# projeto_final.net
KiCad netlist of a schematic drawn in EAGLE
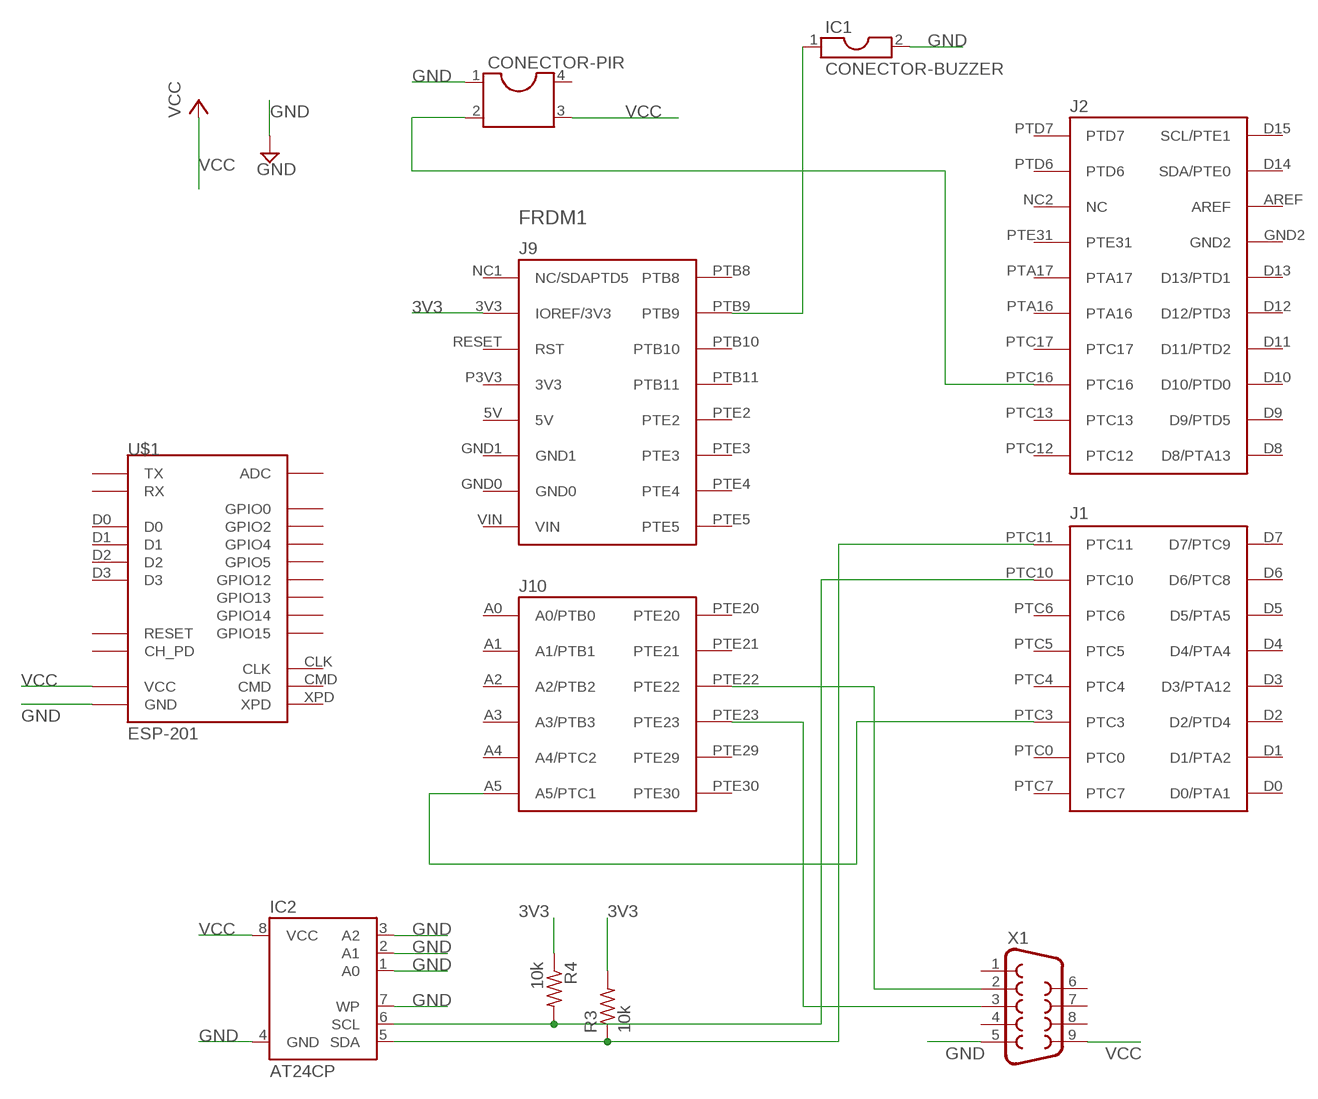
[diagram p0: schematic, sheet 1]

(export (version "E")
  (design (tool "Eeschema 10.0.6"))
  (components
    (comp (ref "CONECTOR-PIR")
      (value "DIL4")
      (footprint "eagle-import:DIL04")
      (libsource (lib "eagle-import") (part "DIL4"))
    )
    (comp (ref "FRDM1")
      (value "FRDM-KL25ZNORMAL")
      (footprint "eagle-import:FRDM_KL25Z_NORMAL")
      (libsource (lib "eagle-import") (part "FRDM-KL25ZNORMAL"))
    )
    (comp (ref "IC1")
      (value "CONECTOR-BUZZER")
      (footprint "eagle-import:DIL02")
      (libsource (lib "eagle-import") (part "DIL2"))
    )
    (comp (ref "IC2")
      (value "AT24CP")
      (footprint "eagle-import:DIL08")
      (fields (field (name "MPN") "AT24C1024BW-SH-B"))
      (libsource (lib "eagle-import") (part "AT24CP"))
    )
    (comp (ref "R3")
      (value "10k")
      (footprint "eagle-import:0204V")
      (libsource (lib "eagle-import") (part "R-US_0204/2V"))
    )
    (comp (ref "R4")
      (value "10k")
      (footprint "eagle-import:0204V")
      (libsource (lib "eagle-import") (part "R-US_0204/2V"))
    )
    (comp (ref "U$1")
      (value "ESP-201")
      (footprint "eagle-import:ESP-201")
      (libsource (lib "eagle-import") (part "ESP-201"))
    )
    (comp (ref "X1")
      (value "F09D")
      (footprint "eagle-import:F09D")
      (libsource (lib "eagle-import") (part "F09D"))
    )
  )
  (nets
    (net (code "1") (name "/3V3") (class "Default")
      (node (ref "FRDM1") (pin "3V3") (pinfunction "IOREF/3V3_3V3") (pintype "bidirectional"))
      (node (ref "R3") (pin "2") (pinfunction "2_2") (pintype "passive"))
      (node (ref "R4") (pin "1") (pinfunction "1_1") (pintype "passive"))
    )
    (net (code "2") (name "GND") (class "Default")
      (node (ref "CONECTOR-PIR") (pin "1") (pinfunction "1_1") (pintype "passive"))
      (node (ref "IC1") (pin "2") (pinfunction "2_2") (pintype "passive"))
      (node (ref "IC2") (pin "1") (pinfunction "A0_1") (pintype "input"))
      (node (ref "IC2") (pin "2") (pinfunction "A1_2") (pintype "input"))
      (node (ref "IC2") (pin "3") (pinfunction "A2_3") (pintype "input"))
      (node (ref "IC2") (pin "4") (pinfunction "GND_4") (pintype "power_in"))
      (node (ref "IC2") (pin "7") (pinfunction "WP_7") (pintype "input"))
      (node (ref "U$1") (pin "GND") (pinfunction "GND_GND") (pintype "bidirectional"))
      (node (ref "U$1") (pin "GND_2") (pinfunction "GND_GND_2") (pintype "bidirectional"))
      (node (ref "U$1") (pin "GND_3") (pinfunction "GND_GND_3") (pintype "bidirectional"))
      (node (ref "X1") (pin "5") (pinfunction "5_5") (pintype "passive"))
    )
    (net (code "3") (name "Net-(CONECTOR-PIR-Pad2)") (class "Default")
      (node (ref "CONECTOR-PIR") (pin "2") (pinfunction "2_2") (pintype "passive"))
      (node (ref "FRDM1") (pin "PTC16") (pinfunction "PTC16_PTC16") (pintype "bidirectional"))
    )
    (net (code "4") (name "Net-(FRDM1-A5{slash}PTC1)") (class "Default")
      (node (ref "FRDM1") (pin "A5") (pinfunction "A5/PTC1_A5") (pintype "bidirectional"))
      (node (ref "FRDM1") (pin "PTC3") (pinfunction "PTC3_PTC3") (pintype "bidirectional"))
    )
    (net (code "5") (name "Net-(FRDM1-PadPTB9)") (class "Default")
      (node (ref "FRDM1") (pin "PTB9") (pinfunction "PTB9_PTB9") (pintype "bidirectional"))
      (node (ref "IC1") (pin "1") (pinfunction "1_1") (pintype "passive"))
    )
    (net (code "6") (name "Net-(FRDM1-PadPTE22)") (class "Default")
      (node (ref "FRDM1") (pin "PTE22") (pinfunction "PTE22_PTE22") (pintype "bidirectional"))
      (node (ref "X1") (pin "2") (pinfunction "2_2") (pintype "passive"))
    )
    (net (code "7") (name "Net-(FRDM1-PadPTE23)") (class "Default")
      (node (ref "FRDM1") (pin "PTE23") (pinfunction "PTE23_PTE23") (pintype "bidirectional"))
      (node (ref "X1") (pin "3") (pinfunction "3_3") (pintype "passive"))
    )
    (net (code "8") (name "Net-(IC2-SCL)") (class "Default")
      (node (ref "FRDM1") (pin "PTC10") (pinfunction "PTC10_PTC10") (pintype "bidirectional"))
      (node (ref "IC2") (pin "6") (pinfunction "SCL_6") (pintype "bidirectional"))
      (node (ref "R4") (pin "2") (pinfunction "2_2") (pintype "passive"))
    )
    (net (code "9") (name "Net-(IC2-SDA)") (class "Default")
      (node (ref "FRDM1") (pin "PTC11") (pinfunction "PTC11_PTC11") (pintype "bidirectional"))
      (node (ref "IC2") (pin "5") (pinfunction "SDA_5") (pintype "bidirectional"))
      (node (ref "R3") (pin "1") (pinfunction "1_1") (pintype "passive"))
    )
    (net (code "10") (name "VCC") (class "Default")
      (node (ref "CONECTOR-PIR") (pin "3") (pinfunction "3_3") (pintype "passive"))
      (node (ref "IC2") (pin "8") (pinfunction "VCC_8") (pintype "power_in"))
      (node (ref "U$1") (pin "3V3") (pinfunction "VCC_3V3") (pintype "bidirectional"))
      (node (ref "U$1") (pin "3V3_2") (pinfunction "VCC_3V3_2") (pintype "bidirectional"))
      (node (ref "U$1") (pin "3V3_3") (pinfunction "VCC_3V3_3") (pintype "bidirectional"))
      (node (ref "X1") (pin "9") (pinfunction "9_9") (pintype "passive"))
    )
    (net (code "11") (name "unconnected-(CONECTOR-PIR-Pad4)") (class "Default")
      (node (ref "CONECTOR-PIR") (pin "4") (pinfunction "4_4") (pintype "passive"))
    )
    (net (code "12") (name "unconnected-(FRDM1-3V3-PadP3V3)") (class "Default")
      (node (ref "FRDM1") (pin "P3V3") (pinfunction "3V3_P3V3") (pintype "bidirectional"))
    )
    (net (code "13") (name "unconnected-(FRDM1-A0{slash}PTB0-PadA0)") (class "Default")
      (node (ref "FRDM1") (pin "A0") (pinfunction "A0/PTB0_A0") (pintype "bidirectional"))
    )
    (net (code "14") (name "unconnected-(FRDM1-A1{slash}PTB1-PadA1)") (class "Default")
      (node (ref "FRDM1") (pin "A1") (pinfunction "A1/PTB1_A1") (pintype "bidirectional"))
    )
    (net (code "15") (name "unconnected-(FRDM1-A2{slash}PTB2-PadA2)") (class "Default")
      (node (ref "FRDM1") (pin "A2") (pinfunction "A2/PTB2_A2") (pintype "bidirectional"))
    )
    (net (code "16") (name "unconnected-(FRDM1-A3{slash}PTB3-PadA3)") (class "Default")
      (node (ref "FRDM1") (pin "A3") (pinfunction "A3/PTB3_A3") (pintype "bidirectional"))
    )
    (net (code "17") (name "unconnected-(FRDM1-A4{slash}PTC2-PadA4)") (class "Default")
      (node (ref "FRDM1") (pin "A4") (pinfunction "A4/PTC2_A4") (pintype "bidirectional"))
    )
    (net (code "18") (name "unconnected-(FRDM1-D0{slash}PTA1-PadD0)") (class "Default")
      (node (ref "FRDM1") (pin "D0") (pinfunction "D0/PTA1_D0") (pintype "bidirectional"))
    )
    (net (code "19") (name "unconnected-(FRDM1-D1{slash}PTA2-PadD1)") (class "Default")
      (node (ref "FRDM1") (pin "D1") (pinfunction "D1/PTA2_D1") (pintype "bidirectional"))
    )
    (net (code "20") (name "unconnected-(FRDM1-D2{slash}PTD4-PadD2)") (class "Default")
      (node (ref "FRDM1") (pin "D2") (pinfunction "D2/PTD4_D2") (pintype "bidirectional"))
    )
    (net (code "21") (name "unconnected-(FRDM1-D3{slash}PTA12-PadD3)") (class "Default")
      (node (ref "FRDM1") (pin "D3") (pinfunction "D3/PTA12_D3") (pintype "bidirectional"))
    )
    (net (code "22") (name "unconnected-(FRDM1-D4{slash}PTA4-PadD4)") (class "Default")
      (node (ref "FRDM1") (pin "D4") (pinfunction "D4/PTA4_D4") (pintype "bidirectional"))
    )
    (net (code "23") (name "unconnected-(FRDM1-D5{slash}PTA5-PadD5)") (class "Default")
      (node (ref "FRDM1") (pin "D5") (pinfunction "D5/PTA5_D5") (pintype "bidirectional"))
    )
    (net (code "24") (name "unconnected-(FRDM1-D6{slash}PTC8-PadD6)") (class "Default")
      (node (ref "FRDM1") (pin "D6") (pinfunction "D6/PTC8_D6") (pintype "bidirectional"))
    )
    (net (code "25") (name "unconnected-(FRDM1-D7{slash}PTC9-PadD7)") (class "Default")
      (node (ref "FRDM1") (pin "D7") (pinfunction "D7/PTC9_D7") (pintype "bidirectional"))
    )
    (net (code "26") (name "unconnected-(FRDM1-D8{slash}PTA13-PadD8)") (class "Default")
      (node (ref "FRDM1") (pin "D8") (pinfunction "D8/PTA13_D8") (pintype "bidirectional"))
    )
    (net (code "27") (name "unconnected-(FRDM1-D9{slash}PTD5-PadD9)") (class "Default")
      (node (ref "FRDM1") (pin "D9") (pinfunction "D9/PTD5_D9") (pintype "bidirectional"))
    )
    (net (code "28") (name "unconnected-(FRDM1-D10{slash}PTD0-PadD10)") (class "Default")
      (node (ref "FRDM1") (pin "D10") (pinfunction "D10/PTD0_D10") (pintype "bidirectional"))
    )
    (net (code "29") (name "unconnected-(FRDM1-D11{slash}PTD2-PadD11)") (class "Default")
      (node (ref "FRDM1") (pin "D11") (pinfunction "D11/PTD2_D11") (pintype "bidirectional"))
    )
    (net (code "30") (name "unconnected-(FRDM1-D12{slash}PTD3-PadD12)") (class "Default")
      (node (ref "FRDM1") (pin "D12") (pinfunction "D12/PTD3_D12") (pintype "bidirectional"))
    )
    (net (code "31") (name "unconnected-(FRDM1-D13{slash}PTD1-PadD13)") (class "Default")
      (node (ref "FRDM1") (pin "D13") (pinfunction "D13/PTD1_D13") (pintype "bidirectional"))
    )
    (net (code "32") (name "unconnected-(FRDM1-NC-PadNC2)") (class "Default")
      (node (ref "FRDM1") (pin "NC2") (pinfunction "NC_NC2") (pintype "bidirectional"))
    )
    (net (code "33") (name "unconnected-(FRDM1-NC{slash}SDAPTD5-PadNC1)") (class "Default")
      (node (ref "FRDM1") (pin "NC1") (pinfunction "NC/SDAPTD5_NC1") (pintype "bidirectional"))
    )
    (net (code "34") (name "unconnected-(FRDM1-Pad5V)") (class "Default")
      (node (ref "FRDM1") (pin "5V") (pinfunction "5V_5V") (pintype "bidirectional"))
    )
    (net (code "35") (name "unconnected-(FRDM1-PadAREF)") (class "Default")
      (node (ref "FRDM1") (pin "AREF") (pinfunction "AREF_AREF") (pintype "bidirectional"))
    )
    (net (code "36") (name "unconnected-(FRDM1-PadGND0)") (class "Default")
      (node (ref "FRDM1") (pin "GND0") (pinfunction "GND0_GND0") (pintype "bidirectional"))
    )
    (net (code "37") (name "unconnected-(FRDM1-PadGND1)") (class "Default")
      (node (ref "FRDM1") (pin "GND1") (pinfunction "GND1_GND1") (pintype "bidirectional"))
    )
    (net (code "38") (name "unconnected-(FRDM1-PadGND2)") (class "Default")
      (node (ref "FRDM1") (pin "GND2") (pinfunction "GND2_GND2") (pintype "bidirectional"))
    )
    (net (code "39") (name "unconnected-(FRDM1-PadPTA16)") (class "Default")
      (node (ref "FRDM1") (pin "PTA16") (pinfunction "PTA16_PTA16") (pintype "bidirectional"))
    )
    (net (code "40") (name "unconnected-(FRDM1-PadPTA17)") (class "Default")
      (node (ref "FRDM1") (pin "PTA17") (pinfunction "PTA17_PTA17") (pintype "bidirectional"))
    )
    (net (code "41") (name "unconnected-(FRDM1-PadPTB8)") (class "Default")
      (node (ref "FRDM1") (pin "PTB8") (pinfunction "PTB8_PTB8") (pintype "bidirectional"))
    )
    (net (code "42") (name "unconnected-(FRDM1-PadPTB10)") (class "Default")
      (node (ref "FRDM1") (pin "PTB10") (pinfunction "PTB10_PTB10") (pintype "bidirectional"))
    )
    (net (code "43") (name "unconnected-(FRDM1-PadPTB11)") (class "Default")
      (node (ref "FRDM1") (pin "PTB11") (pinfunction "PTB11_PTB11") (pintype "bidirectional"))
    )
    (net (code "44") (name "unconnected-(FRDM1-PadPTC0)") (class "Default")
      (node (ref "FRDM1") (pin "PTC0") (pinfunction "PTC0_PTC0") (pintype "bidirectional"))
    )
    (net (code "45") (name "unconnected-(FRDM1-PadPTC4)") (class "Default")
      (node (ref "FRDM1") (pin "PTC4") (pinfunction "PTC4_PTC4") (pintype "bidirectional"))
    )
    (net (code "46") (name "unconnected-(FRDM1-PadPTC5)") (class "Default")
      (node (ref "FRDM1") (pin "PTC5") (pinfunction "PTC5_PTC5") (pintype "bidirectional"))
    )
    (net (code "47") (name "unconnected-(FRDM1-PadPTC6)") (class "Default")
      (node (ref "FRDM1") (pin "PTC6") (pinfunction "PTC6_PTC6") (pintype "bidirectional"))
    )
    (net (code "48") (name "unconnected-(FRDM1-PadPTC7)") (class "Default")
      (node (ref "FRDM1") (pin "PTC7") (pinfunction "PTC7_PTC7") (pintype "bidirectional"))
    )
    (net (code "49") (name "unconnected-(FRDM1-PadPTC12)") (class "Default")
      (node (ref "FRDM1") (pin "PTC12") (pinfunction "PTC12_PTC12") (pintype "bidirectional"))
    )
    (net (code "50") (name "unconnected-(FRDM1-PadPTC13)") (class "Default")
      (node (ref "FRDM1") (pin "PTC13") (pinfunction "PTC13_PTC13") (pintype "bidirectional"))
    )
    (net (code "51") (name "unconnected-(FRDM1-PadPTC17)") (class "Default")
      (node (ref "FRDM1") (pin "PTC17") (pinfunction "PTC17_PTC17") (pintype "bidirectional"))
    )
    (net (code "52") (name "unconnected-(FRDM1-PadPTD6)") (class "Default")
      (node (ref "FRDM1") (pin "PTD6") (pinfunction "PTD6_PTD6") (pintype "bidirectional"))
    )
    (net (code "53") (name "unconnected-(FRDM1-PadPTD7)") (class "Default")
      (node (ref "FRDM1") (pin "PTD7") (pinfunction "PTD7_PTD7") (pintype "bidirectional"))
    )
    (net (code "54") (name "unconnected-(FRDM1-PadPTE2)") (class "Default")
      (node (ref "FRDM1") (pin "PTE2") (pinfunction "PTE2_PTE2") (pintype "bidirectional"))
    )
    (net (code "55") (name "unconnected-(FRDM1-PadPTE3)") (class "Default")
      (node (ref "FRDM1") (pin "PTE3") (pinfunction "PTE3_PTE3") (pintype "bidirectional"))
    )
    (net (code "56") (name "unconnected-(FRDM1-PadPTE4)") (class "Default")
      (node (ref "FRDM1") (pin "PTE4") (pinfunction "PTE4_PTE4") (pintype "bidirectional"))
    )
    (net (code "57") (name "unconnected-(FRDM1-PadPTE5)") (class "Default")
      (node (ref "FRDM1") (pin "PTE5") (pinfunction "PTE5_PTE5") (pintype "bidirectional"))
    )
    (net (code "58") (name "unconnected-(FRDM1-PadPTE20)") (class "Default")
      (node (ref "FRDM1") (pin "PTE20") (pinfunction "PTE20_PTE20") (pintype "bidirectional"))
    )
    (net (code "59") (name "unconnected-(FRDM1-PadPTE21)") (class "Default")
      (node (ref "FRDM1") (pin "PTE21") (pinfunction "PTE21_PTE21") (pintype "bidirectional"))
    )
    (net (code "60") (name "unconnected-(FRDM1-PadPTE29)") (class "Default")
      (node (ref "FRDM1") (pin "PTE29") (pinfunction "PTE29_PTE29") (pintype "bidirectional"))
    )
    (net (code "61") (name "unconnected-(FRDM1-PadPTE30)") (class "Default")
      (node (ref "FRDM1") (pin "PTE30") (pinfunction "PTE30_PTE30") (pintype "bidirectional"))
    )
    (net (code "62") (name "unconnected-(FRDM1-PadPTE31)") (class "Default")
      (node (ref "FRDM1") (pin "PTE31") (pinfunction "PTE31_PTE31") (pintype "bidirectional"))
    )
    (net (code "63") (name "unconnected-(FRDM1-PadVIN)") (class "Default")
      (node (ref "FRDM1") (pin "VIN") (pinfunction "VIN_VIN") (pintype "bidirectional"))
    )
    (net (code "64") (name "unconnected-(FRDM1-RST-PadRESET)") (class "Default")
      (node (ref "FRDM1") (pin "RESET") (pinfunction "RST_RESET") (pintype "bidirectional"))
    )
    (net (code "65") (name "unconnected-(FRDM1-SCL{slash}PTE1-PadD15)") (class "Default")
      (node (ref "FRDM1") (pin "D15") (pinfunction "SCL/PTE1_D15") (pintype "bidirectional"))
    )
    (net (code "66") (name "unconnected-(FRDM1-SDA{slash}PTE0-PadD14)") (class "Default")
      (node (ref "FRDM1") (pin "D14") (pinfunction "SDA/PTE0_D14") (pintype "bidirectional"))
    )
    (net (code "67") (name "unconnected-(U$1-PadADC)") (class "Default")
      (node (ref "U$1") (pin "ADC") (pinfunction "ADC_ADC") (pintype "bidirectional"))
    )
    (net (code "68") (name "unconnected-(U$1-PadCH_PD)") (class "Default")
      (node (ref "U$1") (pin "CH_PD") (pinfunction "CH_PD_CH_PD") (pintype "bidirectional"))
    )
    (net (code "69") (name "unconnected-(U$1-PadCLK)") (class "Default")
      (node (ref "U$1") (pin "CLK") (pinfunction "CLK_CLK") (pintype "bidirectional"))
    )
    (net (code "70") (name "unconnected-(U$1-PadCMD)") (class "Default")
      (node (ref "U$1") (pin "CMD") (pinfunction "CMD_CMD") (pintype "bidirectional"))
    )
    (net (code "71") (name "unconnected-(U$1-PadD0)") (class "Default")
      (node (ref "U$1") (pin "D0") (pinfunction "D0_D0") (pintype "bidirectional"))
    )
    (net (code "72") (name "unconnected-(U$1-PadD1)") (class "Default")
      (node (ref "U$1") (pin "D1") (pinfunction "D1_D1") (pintype "bidirectional"))
    )
    (net (code "73") (name "unconnected-(U$1-PadD2)") (class "Default")
      (node (ref "U$1") (pin "D2") (pinfunction "D2_D2") (pintype "bidirectional"))
    )
    (net (code "74") (name "unconnected-(U$1-PadD3)") (class "Default")
      (node (ref "U$1") (pin "D3") (pinfunction "D3_D3") (pintype "bidirectional"))
    )
    (net (code "75") (name "unconnected-(U$1-PadGPIO0)") (class "Default")
      (node (ref "U$1") (pin "GPIO0") (pinfunction "GPIO0_GPIO0") (pintype "bidirectional"))
    )
    (net (code "76") (name "unconnected-(U$1-PadGPIO2)") (class "Default")
      (node (ref "U$1") (pin "GPIO2") (pinfunction "GPIO2_GPIO2") (pintype "bidirectional"))
    )
    (net (code "77") (name "unconnected-(U$1-PadGPIO4)") (class "Default")
      (node (ref "U$1") (pin "GPIO4") (pinfunction "GPIO4_GPIO4") (pintype "bidirectional"))
    )
    (net (code "78") (name "unconnected-(U$1-PadGPIO5)") (class "Default")
      (node (ref "U$1") (pin "GPIO5") (pinfunction "GPIO5_GPIO5") (pintype "bidirectional"))
    )
    (net (code "79") (name "unconnected-(U$1-PadGPIO12)") (class "Default")
      (node (ref "U$1") (pin "GPIO12") (pinfunction "GPIO12_GPIO12") (pintype "bidirectional"))
    )
    (net (code "80") (name "unconnected-(U$1-PadGPIO13)") (class "Default")
      (node (ref "U$1") (pin "GPIO13") (pinfunction "GPIO13_GPIO13") (pintype "bidirectional"))
    )
    (net (code "81") (name "unconnected-(U$1-PadGPIO14)") (class "Default")
      (node (ref "U$1") (pin "GPIO14") (pinfunction "GPIO14_GPIO14") (pintype "bidirectional"))
    )
    (net (code "82") (name "unconnected-(U$1-PadGPIO15)") (class "Default")
      (node (ref "U$1") (pin "GPIO15") (pinfunction "GPIO15_GPIO15") (pintype "bidirectional"))
    )
    (net (code "83") (name "unconnected-(U$1-PadRX)") (class "Default")
      (node (ref "U$1") (pin "RX") (pinfunction "RX_RX") (pintype "bidirectional"))
    )
    (net (code "84") (name "unconnected-(U$1-PadTX)") (class "Default")
      (node (ref "U$1") (pin "TX") (pinfunction "TX_TX") (pintype "bidirectional"))
    )
    (net (code "85") (name "unconnected-(U$1-PadXPD)") (class "Default")
      (node (ref "U$1") (pin "XPD") (pinfunction "XPD_XPD") (pintype "bidirectional"))
    )
    (net (code "86") (name "unconnected-(U$1-RESET-PadRST)") (class "Default")
      (node (ref "U$1") (pin "RST") (pinfunction "RESET_RST") (pintype "bidirectional"))
    )
    (net (code "87") (name "unconnected-(X1-Pad1)") (class "Default")
      (node (ref "X1") (pin "1") (pinfunction "1_1") (pintype "passive"))
    )
    (net (code "88") (name "unconnected-(X1-Pad4)") (class "Default")
      (node (ref "X1") (pin "4") (pinfunction "4_4") (pintype "passive"))
    )
    (net (code "89") (name "unconnected-(X1-Pad6)") (class "Default")
      (node (ref "X1") (pin "6") (pinfunction "6_6") (pintype "passive"))
    )
    (net (code "90") (name "unconnected-(X1-Pad7)") (class "Default")
      (node (ref "X1") (pin "7") (pinfunction "7_7") (pintype "passive"))
    )
    (net (code "91") (name "unconnected-(X1-Pad8)") (class "Default")
      (node (ref "X1") (pin "8") (pinfunction "8_8") (pintype "passive"))
    )
  )
)
